# Microcontroller.net
KiCad netlist of a schematic drawn in Altium Designer
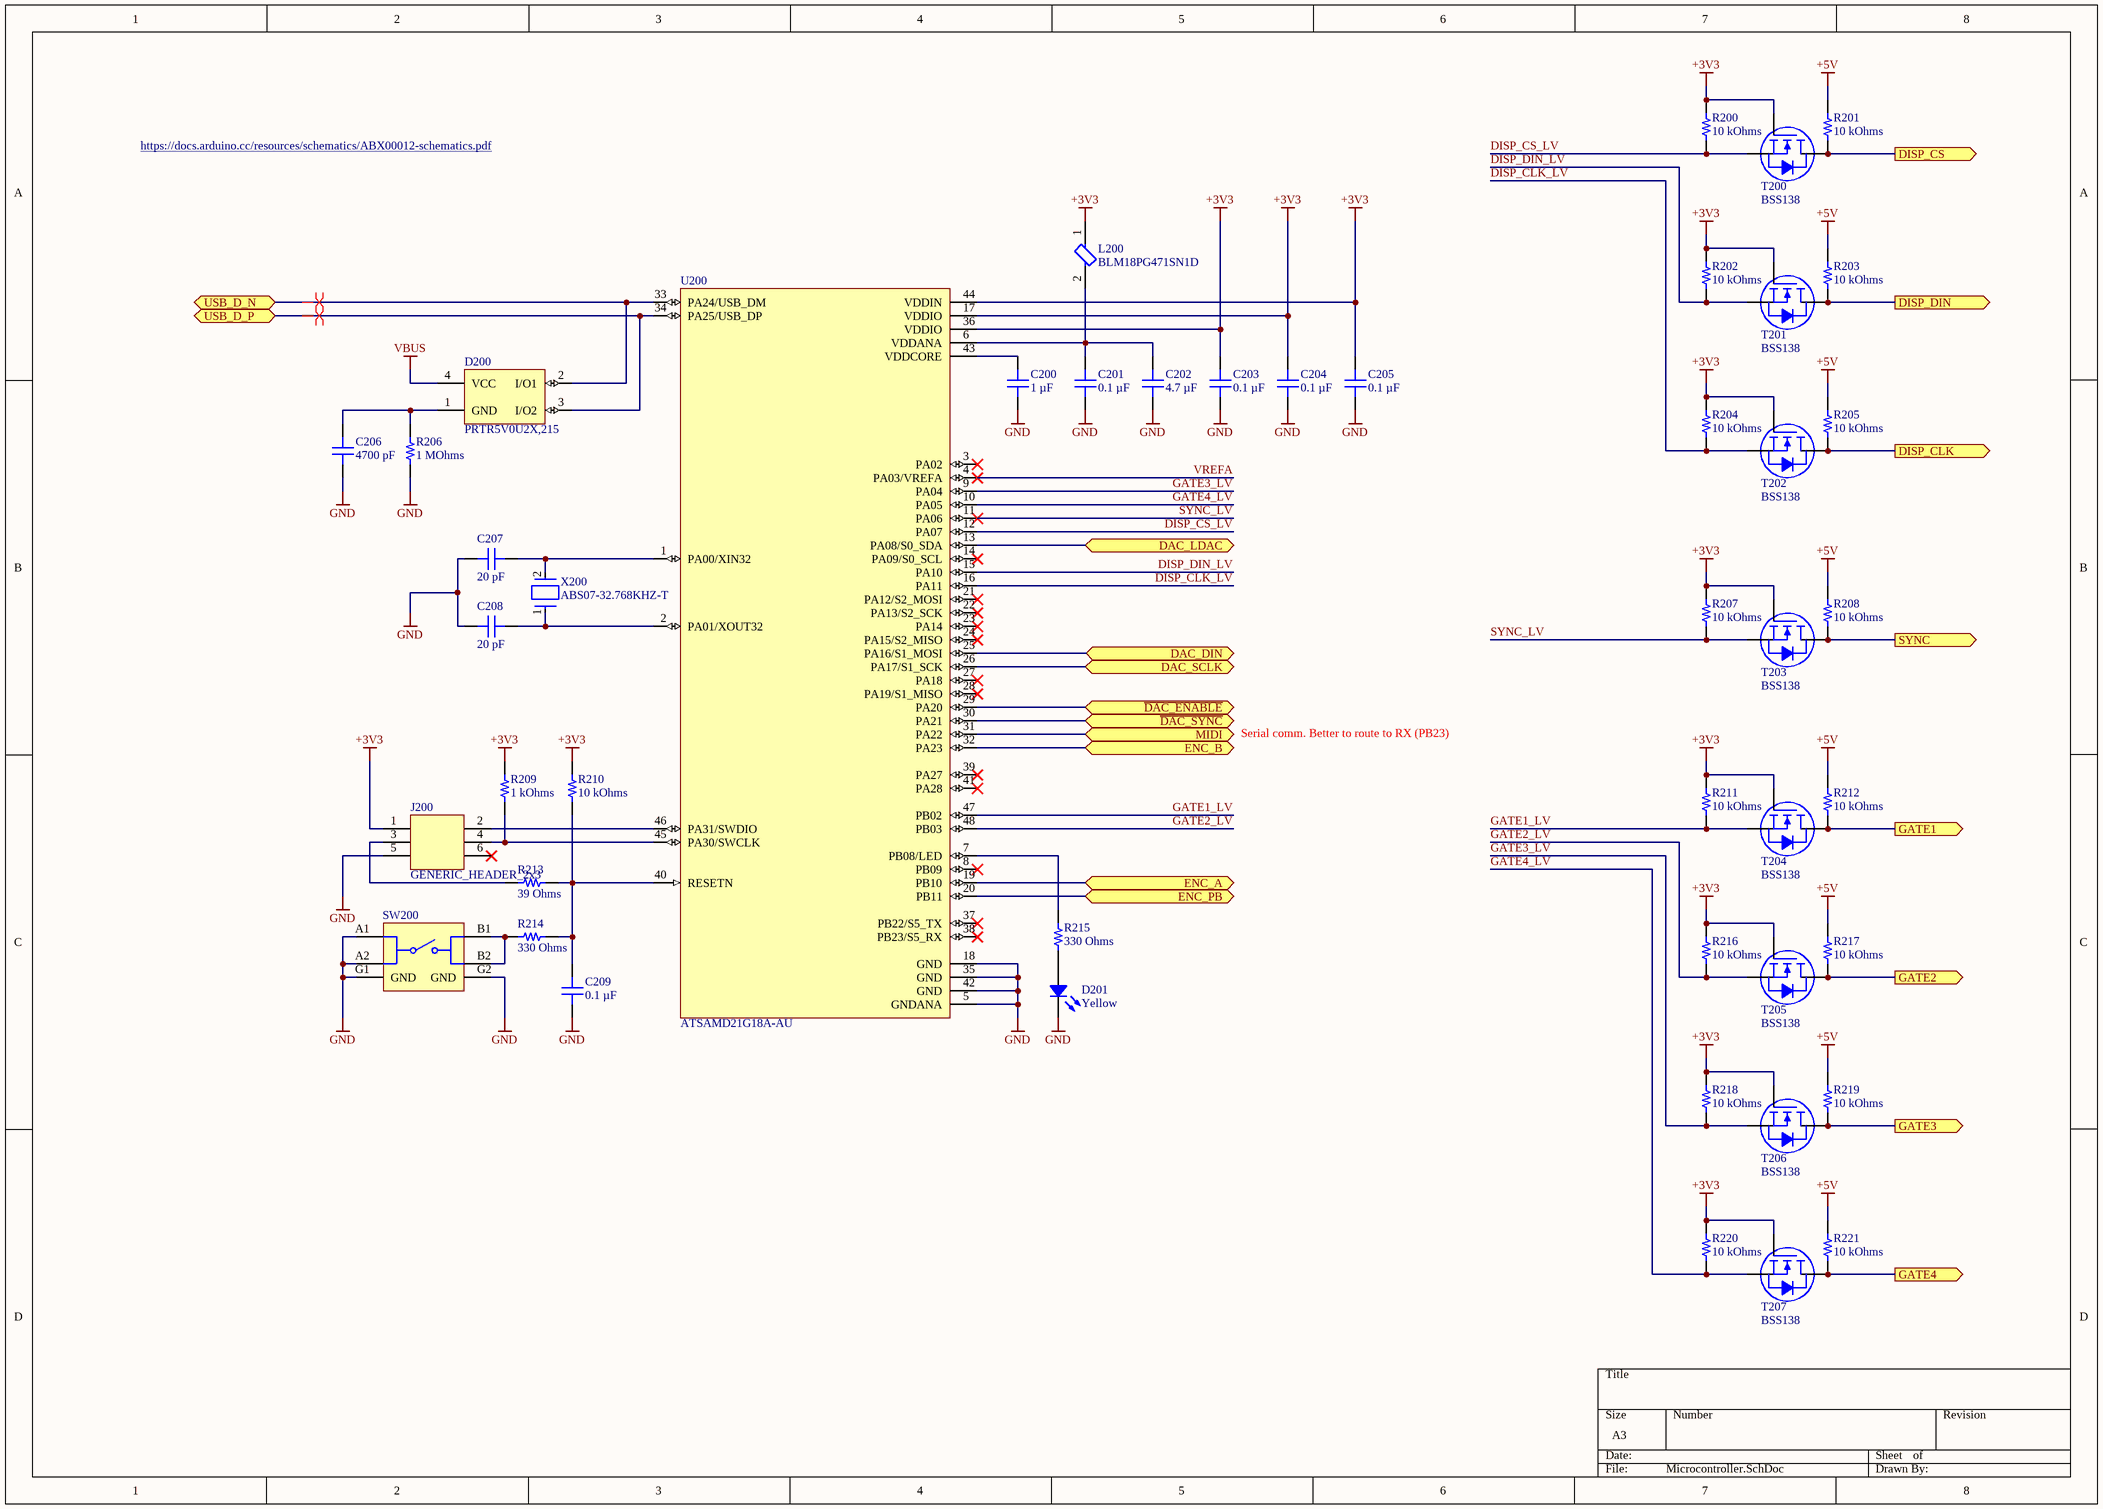
[diagram p0: Microcontroller.SchDoc]

(export (version "E")
  (design (tool "Eeschema 10.0.6"))
  (components
    (comp (ref "C200")
      (value "1 µF")
      (footprint "CAP 0603_1608")
      (description "CAP CER 1UF 10V X7R 0603")
      (fields (field (name "PART NUMBER") "CC0603KRX7R6BB105") (field (name "MANUFACTURER") "Yageo"))
      (libsource (lib "Celestial Altium Library") (part "Capacitor"))
    )
    (comp (ref "C201")
      (value "0.1 µF")
      (footprint "CAP 0603_1608")
      (description "CAP CER 0.1UF 16V X7R 0603")
      (fields (field (name "PART NUMBER") "CS0603KRX7R7BB104") (field (name "MANUFACTURER") "Yageo"))
      (libsource (lib "Celestial Altium Library") (part "Capacitor"))
    )
    (comp (ref "C202")
      (value "4.7 µF")
      (footprint "CAP 0603_1608")
      (description "CAP CER 4.7UF 10V X5R 0603")
      (fields (field (name "PART NUMBER") "CC0603MRX5R6BB475") (field (name "MANUFACTURER") "Yageo"))
      (libsource (lib "Celestial Altium Library") (part "Capacitor"))
    )
    (comp (ref "C203")
      (value "0.1 µF")
      (footprint "CAP 0603_1608")
      (description "CAP CER 0.1UF 16V X7R 0603")
      (fields (field (name "PART NUMBER") "CS0603KRX7R7BB104") (field (name "MANUFACTURER") "Yageo"))
      (libsource (lib "Celestial Altium Library") (part "Capacitor"))
    )
    (comp (ref "C204")
      (value "0.1 µF")
      (footprint "CAP 0603_1608")
      (description "CAP CER 0.1UF 16V X7R 0603")
      (fields (field (name "PART NUMBER") "CS0603KRX7R7BB104") (field (name "MANUFACTURER") "Yageo"))
      (libsource (lib "Celestial Altium Library") (part "Capacitor"))
    )
    (comp (ref "C205")
      (value "0.1 µF")
      (footprint "CAP 0603_1608")
      (description "CAP CER 0.1UF 16V X7R 0603")
      (fields (field (name "PART NUMBER") "CS0603KRX7R7BB104") (field (name "MANUFACTURER") "Yageo"))
      (libsource (lib "Celestial Altium Library") (part "Capacitor"))
    )
    (comp (ref "C206")
      (value "4700 pF")
      (footprint "CAP 0603_1608")
      (description "CAP CER 4700PF 50V X7R 0603")
      (fields (field (name "PART NUMBER") "CC0603JRX7R9BB472") (field (name "MANUFACTURER") "Yageo"))
      (libsource (lib "Celestial Altium Library") (part "Capacitor"))
    )
    (comp (ref "C207")
      (value "20 pF")
      (footprint "CAP 0603_1608")
      (description "CAP CER 20PF 50V C0G/NPO 0603")
      (fields (field (name "PART NUMBER") "CC0603JRNPO9BN200") (field (name "MANUFACTURER") "Yageo"))
      (libsource (lib "Celestial Altium Library") (part "Capacitor"))
    )
    (comp (ref "C208")
      (value "20 pF")
      (footprint "CAP 0603_1608")
      (description "CAP CER 20PF 50V C0G/NPO 0603")
      (fields (field (name "PART NUMBER") "CC0603JRNPO9BN200") (field (name "MANUFACTURER") "Yageo"))
      (libsource (lib "Celestial Altium Library") (part "Capacitor"))
    )
    (comp (ref "C209")
      (value "0.1 µF")
      (footprint "CAP 0603_1608")
      (description "CAP CER 0.1UF 16V X7R 0603")
      (fields (field (name "PART NUMBER") "CS0603KRX7R7BB104") (field (name "MANUFACTURER") "Yageo"))
      (libsource (lib "Celestial Altium Library") (part "Capacitor"))
    )
    (comp (ref "D200")
      (value "PRTR5V0U2X,215")
      (footprint "NXP-SOT143B-4_V")
      (fields (field (name "MANUFACTURER") "NXP Semiconductors"))
      (libsource (lib "LabratsSynthLib") (part "PRTR5V0U2X,215"))
    )
    (comp (ref "D201")
      (value "Yellow")
      (footprint "LED 0603_1608 YELLOW")
      (description "LED YELLOW 0603 SMD")
      (fields (field (name "PART NUMBER") "5990040007F") (field (name "MANUFACTURER") "Dialight"))
      (libsource (lib "Celestial Altium Library") (part "LED"))
    )
    (comp (ref "J200")
      (value "GENERIC_HEADER_2x3")
      (footprint "HEADER_2x3_TH_MALE")
      (libsource (lib "LabratsSynthLib") (part "GENERIC_HEADER_2x3"))
    )
    (comp (ref "L200")
      (value "BLM18PG471SN1D")
      (footprint "FP-BLM18-0_15-t0_8-MFG")
      (description "Chip Ferrite Bead, 0603, 470Ω @ 100MHz, 0.2Ω, 25%, 1A")
      (fields (field (name "TOLERANCE") "25%"))
      (libsource (lib "Altium Content Vault") (part "5f30dd21d616792df468990f7003faa"))
    )
    (comp (ref "R200")
      (value "10 kOhms")
      (footprint "RES 0603_1608")
      (description "RES SMD 10K OHM 1% 1/10W 0603")
      (fields (field (name "PART NUMBER") "CRCW060310K0FKTA") (field (name "MANUFACTURER") "Vishay Dale"))
      (libsource (lib "Celestial Altium Library") (part "Resistor"))
    )
    (comp (ref "R201")
      (value "10 kOhms")
      (footprint "RES 0603_1608")
      (description "RES SMD 10K OHM 1% 1/10W 0603")
      (fields (field (name "PART NUMBER") "CRCW060310K0FKTA") (field (name "MANUFACTURER") "Vishay Dale"))
      (libsource (lib "Celestial Altium Library") (part "Resistor"))
    )
    (comp (ref "R202")
      (value "10 kOhms")
      (footprint "RES 0603_1608")
      (description "RES SMD 10K OHM 1% 1/10W 0603")
      (fields (field (name "PART NUMBER") "CRCW060310K0FKTA") (field (name "MANUFACTURER") "Vishay Dale"))
      (libsource (lib "Celestial Altium Library") (part "Resistor"))
    )
    (comp (ref "R203")
      (value "10 kOhms")
      (footprint "RES 0603_1608")
      (description "RES SMD 10K OHM 1% 1/10W 0603")
      (fields (field (name "PART NUMBER") "CRCW060310K0FKTA") (field (name "MANUFACTURER") "Vishay Dale"))
      (libsource (lib "Celestial Altium Library") (part "Resistor"))
    )
    (comp (ref "R204")
      (value "10 kOhms")
      (footprint "RES 0603_1608")
      (description "RES SMD 10K OHM 1% 1/10W 0603")
      (fields (field (name "PART NUMBER") "CRCW060310K0FKTA") (field (name "MANUFACTURER") "Vishay Dale"))
      (libsource (lib "Celestial Altium Library") (part "Resistor"))
    )
    (comp (ref "R205")
      (value "10 kOhms")
      (footprint "RES 0603_1608")
      (description "RES SMD 10K OHM 1% 1/10W 0603")
      (fields (field (name "PART NUMBER") "CRCW060310K0FKTA") (field (name "MANUFACTURER") "Vishay Dale"))
      (libsource (lib "Celestial Altium Library") (part "Resistor"))
    )
    (comp (ref "R206")
      (value "1 MOhms")
      (footprint "RES 0603_1608")
      (description "RES SMD 1M OHM 1% 1/10W 0603")
      (fields (field (name "PART NUMBER") "CRCW06031M00FKEA") (field (name "MANUFACTURER") "Vishay Dale"))
      (libsource (lib "Celestial Altium Library") (part "Resistor"))
    )
    (comp (ref "R207")
      (value "10 kOhms")
      (footprint "RES 0603_1608")
      (description "RES SMD 10K OHM 1% 1/10W 0603")
      (fields (field (name "PART NUMBER") "CRCW060310K0FKTA") (field (name "MANUFACTURER") "Vishay Dale"))
      (libsource (lib "Celestial Altium Library") (part "Resistor"))
    )
    (comp (ref "R208")
      (value "10 kOhms")
      (footprint "RES 0603_1608")
      (description "RES SMD 10K OHM 1% 1/10W 0603")
      (fields (field (name "PART NUMBER") "CRCW060310K0FKTA") (field (name "MANUFACTURER") "Vishay Dale"))
      (libsource (lib "Celestial Altium Library") (part "Resistor"))
    )
    (comp (ref "R209")
      (value "1 kOhms")
      (footprint "RES 0603_1608")
      (description "RES SMD 1K OHM 1% 1/10W 0603")
      (fields (field (name "PART NUMBER") "CRCW06031K00FKEB") (field (name "MANUFACTURER") "Vishay Dale"))
      (libsource (lib "Celestial Altium Library") (part "Resistor"))
    )
    (comp (ref "R210")
      (value "10 kOhms")
      (footprint "RES 0603_1608")
      (description "RES SMD 10K OHM 1% 1/10W 0603")
      (fields (field (name "PART NUMBER") "CRCW060310K0FKTA") (field (name "MANUFACTURER") "Vishay Dale"))
      (libsource (lib "Celestial Altium Library") (part "Resistor"))
    )
    (comp (ref "R211")
      (value "10 kOhms")
      (footprint "RES 0603_1608")
      (description "RES SMD 10K OHM 1% 1/10W 0603")
      (fields (field (name "PART NUMBER") "CRCW060310K0FKTA") (field (name "MANUFACTURER") "Vishay Dale"))
      (libsource (lib "Celestial Altium Library") (part "Resistor"))
    )
    (comp (ref "R212")
      (value "10 kOhms")
      (footprint "RES 0603_1608")
      (description "RES SMD 10K OHM 1% 1/10W 0603")
      (fields (field (name "PART NUMBER") "CRCW060310K0FKTA") (field (name "MANUFACTURER") "Vishay Dale"))
      (libsource (lib "Celestial Altium Library") (part "Resistor"))
    )
    (comp (ref "R213")
      (value "39 Ohms")
      (footprint "RES 0603_1608")
      (description "RES SMD 39 OHM 1% 1/10W 0603")
      (fields (field (name "PART NUMBER") "CRCW060339R0FKEA") (field (name "MANUFACTURER") "Vishay Dale"))
      (libsource (lib "Celestial Altium Library") (part "Resistor"))
    )
    (comp (ref "R214")
      (value "330 Ohms")
      (footprint "RES 0603_1608")
      (description "RES 330 OHM 1% 1/10W 0603")
      (fields (field (name "PART NUMBER") "CRCW0603330RFKEAC") (field (name "MANUFACTURER") "Vishay Dale"))
      (libsource (lib "Celestial Altium Library") (part "Resistor"))
    )
    (comp (ref "R215")
      (value "330 Ohms")
      (footprint "RES 0603_1608")
      (description "RES 330 OHM 1% 1/10W 0603")
      (fields (field (name "PART NUMBER") "CRCW0603330RFKEAC") (field (name "MANUFACTURER") "Vishay Dale"))
      (libsource (lib "Celestial Altium Library") (part "Resistor"))
    )
    (comp (ref "R216")
      (value "10 kOhms")
      (footprint "RES 0603_1608")
      (description "RES SMD 10K OHM 1% 1/10W 0603")
      (fields (field (name "PART NUMBER") "CRCW060310K0FKTA") (field (name "MANUFACTURER") "Vishay Dale"))
      (libsource (lib "Celestial Altium Library") (part "Resistor"))
    )
    (comp (ref "R217")
      (value "10 kOhms")
      (footprint "RES 0603_1608")
      (description "RES SMD 10K OHM 1% 1/10W 0603")
      (fields (field (name "PART NUMBER") "CRCW060310K0FKTA") (field (name "MANUFACTURER") "Vishay Dale"))
      (libsource (lib "Celestial Altium Library") (part "Resistor"))
    )
    (comp (ref "R218")
      (value "10 kOhms")
      (footprint "RES 0603_1608")
      (description "RES SMD 10K OHM 1% 1/10W 0603")
      (fields (field (name "PART NUMBER") "CRCW060310K0FKTA") (field (name "MANUFACTURER") "Vishay Dale"))
      (libsource (lib "Celestial Altium Library") (part "Resistor"))
    )
    (comp (ref "R219")
      (value "10 kOhms")
      (footprint "RES 0603_1608")
      (description "RES SMD 10K OHM 1% 1/10W 0603")
      (fields (field (name "PART NUMBER") "CRCW060310K0FKTA") (field (name "MANUFACTURER") "Vishay Dale"))
      (libsource (lib "Celestial Altium Library") (part "Resistor"))
    )
    (comp (ref "R220")
      (value "10 kOhms")
      (footprint "RES 0603_1608")
      (description "RES SMD 10K OHM 1% 1/10W 0603")
      (fields (field (name "PART NUMBER") "CRCW060310K0FKTA") (field (name "MANUFACTURER") "Vishay Dale"))
      (libsource (lib "Celestial Altium Library") (part "Resistor"))
    )
    (comp (ref "R221")
      (value "10 kOhms")
      (footprint "RES 0603_1608")
      (description "RES SMD 10K OHM 1% 1/10W 0603")
      (fields (field (name "PART NUMBER") "CRCW060310K0FKTA") (field (name "MANUFACTURER") "Vishay Dale"))
      (libsource (lib "Celestial Altium Library") (part "Resistor"))
    )
    (comp (ref "SW200")
      (value "435171014816")
      (footprint "435171014816")
      (description "Tactile Switch, Spst-no, 0.05A, 12V, SMD;")
      (libsource (lib "Altium Content Vault") (part "SPST-NO_4P_2GND"))
    )
    (comp (ref "T200")
      (value "BSS138")
      (footprint "ON SEMI SOT-23-3")
      (description "MOSFET N-CH 50V 220MA SOT-23")
      (fields (field (name "MANUFACTURER") "ON Semiconductor"))
      (libsource (lib "Celestial Altium Library") (part "ON SEMI MOSFET N-CH SOT-23-3"))
    )
    (comp (ref "T201")
      (value "BSS138")
      (footprint "ON SEMI SOT-23-3")
      (description "MOSFET N-CH 50V 220MA SOT-23")
      (fields (field (name "MANUFACTURER") "ON Semiconductor"))
      (libsource (lib "Celestial Altium Library") (part "ON SEMI MOSFET N-CH SOT-23-3"))
    )
    (comp (ref "T202")
      (value "BSS138")
      (footprint "ON SEMI SOT-23-3")
      (description "MOSFET N-CH 50V 220MA SOT-23")
      (fields (field (name "MANUFACTURER") "ON Semiconductor"))
      (libsource (lib "Celestial Altium Library") (part "ON SEMI MOSFET N-CH SOT-23-3"))
    )
    (comp (ref "T203")
      (value "BSS138")
      (footprint "ON SEMI SOT-23-3")
      (description "MOSFET N-CH 50V 220MA SOT-23")
      (fields (field (name "MANUFACTURER") "ON Semiconductor"))
      (libsource (lib "Celestial Altium Library") (part "ON SEMI MOSFET N-CH SOT-23-3"))
    )
    (comp (ref "T204")
      (value "BSS138")
      (footprint "ON SEMI SOT-23-3")
      (description "MOSFET N-CH 50V 220MA SOT-23")
      (fields (field (name "MANUFACTURER") "ON Semiconductor"))
      (libsource (lib "Celestial Altium Library") (part "ON SEMI MOSFET N-CH SOT-23-3"))
    )
    (comp (ref "T205")
      (value "BSS138")
      (footprint "ON SEMI SOT-23-3")
      (description "MOSFET N-CH 50V 220MA SOT-23")
      (fields (field (name "MANUFACTURER") "ON Semiconductor"))
      (libsource (lib "Celestial Altium Library") (part "ON SEMI MOSFET N-CH SOT-23-3"))
    )
    (comp (ref "T206")
      (value "BSS138")
      (footprint "ON SEMI SOT-23-3")
      (description "MOSFET N-CH 50V 220MA SOT-23")
      (fields (field (name "MANUFACTURER") "ON Semiconductor"))
      (libsource (lib "Celestial Altium Library") (part "ON SEMI MOSFET N-CH SOT-23-3"))
    )
    (comp (ref "T207")
      (value "BSS138")
      (footprint "ON SEMI SOT-23-3")
      (description "MOSFET N-CH 50V 220MA SOT-23")
      (fields (field (name "MANUFACTURER") "ON Semiconductor"))
      (libsource (lib "Celestial Altium Library") (part "ON SEMI MOSFET N-CH SOT-23-3"))
    )
    (comp (ref "U200")
      (value "ATSAMD21G18A-AU")
      (footprint "ATML-TQFP48")
      (fields (field (name "MANUFACTURER") "Atmel"))
      (libsource (lib "LabratsSynthLib") (part "ATSAMD21G18A-AU"))
    )
    (comp (ref "X200")
      (value "ABS07-32.768KHZ-T")
      (footprint "FP-ABS07-MFG")
      (description "Crystal 32.768kHz ±20ppm (Tol) 12.5pF FUND 70kΩ 2-Pin CSMD T/R")
      (fields (field (name "TOLERANCE") "20ppm"))
      (libsource (lib "Altium Content Vault") (part "c23a69dc6c9e2f18f2079038eb95dd1"))
    )
  )
  (nets
    (net (code "1") (name "+3V3") (class "Default")
      (node (ref "C203") (pin "2") (pinfunction "2_2") (pintype "passive"))
      (node (ref "C204") (pin "2") (pinfunction "2_2") (pintype "passive"))
      (node (ref "C205") (pin "2") (pinfunction "2_2") (pintype "passive"))
      (node (ref "J200") (pin "1") (pinfunction "1_1") (pintype "passive"))
      (node (ref "L200") (pin "1") (pinfunction "1_1") (pintype "passive"))
      (node (ref "R200") (pin "2") (pinfunction "2_2") (pintype "passive"))
      (node (ref "R202") (pin "2") (pinfunction "2_2") (pintype "passive"))
      (node (ref "R204") (pin "2") (pinfunction "2_2") (pintype "passive"))
      (node (ref "R207") (pin "2") (pinfunction "2_2") (pintype "passive"))
      (node (ref "R209") (pin "2") (pinfunction "2_2") (pintype "passive"))
      (node (ref "R210") (pin "2") (pinfunction "2_2") (pintype "passive"))
      (node (ref "R211") (pin "2") (pinfunction "2_2") (pintype "passive"))
      (node (ref "R216") (pin "2") (pinfunction "2_2") (pintype "passive"))
      (node (ref "R218") (pin "2") (pinfunction "2_2") (pintype "passive"))
      (node (ref "R220") (pin "2") (pinfunction "2_2") (pintype "passive"))
      (node (ref "T200") (pin "1") (pinfunction "G_1") (pintype "passive"))
      (node (ref "T201") (pin "1") (pinfunction "G_1") (pintype "passive"))
      (node (ref "T202") (pin "1") (pinfunction "G_1") (pintype "passive"))
      (node (ref "T203") (pin "1") (pinfunction "G_1") (pintype "passive"))
      (node (ref "T204") (pin "1") (pinfunction "G_1") (pintype "passive"))
      (node (ref "T205") (pin "1") (pinfunction "G_1") (pintype "passive"))
      (node (ref "T206") (pin "1") (pinfunction "G_1") (pintype "passive"))
      (node (ref "T207") (pin "1") (pinfunction "G_1") (pintype "passive"))
      (node (ref "U200") (pin "17") (pinfunction "VDDIO_17") (pintype "power_in"))
      (node (ref "U200") (pin "36") (pinfunction "VDDIO_36") (pintype "power_in"))
      (node (ref "U200") (pin "44") (pinfunction "VDDIN_44") (pintype "power_in"))
    )
    (net (code "2") (name "+5V") (class "Default")
      (node (ref "R201") (pin "2") (pinfunction "2_2") (pintype "passive"))
      (node (ref "R203") (pin "2") (pinfunction "2_2") (pintype "passive"))
      (node (ref "R205") (pin "2") (pinfunction "2_2") (pintype "passive"))
      (node (ref "R208") (pin "2") (pinfunction "2_2") (pintype "passive"))
      (node (ref "R212") (pin "2") (pinfunction "2_2") (pintype "passive"))
      (node (ref "R217") (pin "2") (pinfunction "2_2") (pintype "passive"))
      (node (ref "R219") (pin "2") (pinfunction "2_2") (pintype "passive"))
      (node (ref "R221") (pin "2") (pinfunction "2_2") (pintype "passive"))
    )
    (net (code "3") (name "/DAC_DIN") (class "Default")
      (node (ref "U200") (pin "25") (pinfunction "PA16/S1_MOSI_25") (pintype "bidirectional"))
    )
    (net (code "4") (name "/DAC_LDAC") (class "Default")
      (node (ref "U200") (pin "13") (pinfunction "PA08/S0_SDA_13") (pintype "bidirectional"))
    )
    (net (code "5") (name "/DAC_SCLK") (class "Default")
      (node (ref "U200") (pin "26") (pinfunction "PA17/S1_SCK_26") (pintype "bidirectional"))
    )
    (net (code "6") (name "/DISP_CLK") (class "Default")
      (node (ref "R205") (pin "1") (pinfunction "1_1") (pintype "passive"))
      (node (ref "T202") (pin "3") (pinfunction "D_3") (pintype "passive"))
    )
    (net (code "7") (name "/DISP_CLK_LV") (class "Default")
      (node (ref "R204") (pin "1") (pinfunction "1_1") (pintype "passive"))
      (node (ref "T202") (pin "2") (pinfunction "S_2") (pintype "passive"))
      (node (ref "U200") (pin "16") (pinfunction "PA11_16") (pintype "bidirectional"))
    )
    (net (code "8") (name "/DISP_CS") (class "Default")
      (node (ref "R201") (pin "1") (pinfunction "1_1") (pintype "passive"))
      (node (ref "T200") (pin "3") (pinfunction "D_3") (pintype "passive"))
    )
    (net (code "9") (name "/DISP_CS_LV") (class "Default")
      (node (ref "R200") (pin "1") (pinfunction "1_1") (pintype "passive"))
      (node (ref "T200") (pin "2") (pinfunction "S_2") (pintype "passive"))
      (node (ref "U200") (pin "12") (pinfunction "PA07_12") (pintype "bidirectional"))
    )
    (net (code "10") (name "/DISP_DIN") (class "Default")
      (node (ref "R203") (pin "1") (pinfunction "1_1") (pintype "passive"))
      (node (ref "T201") (pin "3") (pinfunction "D_3") (pintype "passive"))
    )
    (net (code "11") (name "/DISP_DIN_LV") (class "Default")
      (node (ref "R202") (pin "1") (pinfunction "1_1") (pintype "passive"))
      (node (ref "T201") (pin "2") (pinfunction "S_2") (pintype "passive"))
      (node (ref "U200") (pin "15") (pinfunction "PA10_15") (pintype "bidirectional"))
    )
    (net (code "12") (name "/ENC_A") (class "Default")
      (node (ref "U200") (pin "19") (pinfunction "PB10_19") (pintype "bidirectional"))
    )
    (net (code "13") (name "/ENC_B") (class "Default")
      (node (ref "U200") (pin "32") (pinfunction "PA23_32") (pintype "bidirectional"))
    )
    (net (code "14") (name "/ENC_PB") (class "Default")
      (node (ref "U200") (pin "20") (pinfunction "PB11_20") (pintype "bidirectional"))
    )
    (net (code "15") (name "/GATE1") (class "Default")
      (node (ref "R212") (pin "1") (pinfunction "1_1") (pintype "passive"))
      (node (ref "T204") (pin "3") (pinfunction "D_3") (pintype "passive"))
    )
    (net (code "16") (name "/GATE1_LV") (class "Default")
      (node (ref "R211") (pin "1") (pinfunction "1_1") (pintype "passive"))
      (node (ref "T204") (pin "2") (pinfunction "S_2") (pintype "passive"))
      (node (ref "U200") (pin "47") (pinfunction "PB02_47") (pintype "bidirectional"))
    )
    (net (code "17") (name "/GATE2") (class "Default")
      (node (ref "R217") (pin "1") (pinfunction "1_1") (pintype "passive"))
      (node (ref "T205") (pin "3") (pinfunction "D_3") (pintype "passive"))
    )
    (net (code "18") (name "/GATE2_LV") (class "Default")
      (node (ref "R216") (pin "1") (pinfunction "1_1") (pintype "passive"))
      (node (ref "T205") (pin "2") (pinfunction "S_2") (pintype "passive"))
      (node (ref "U200") (pin "48") (pinfunction "PB03_48") (pintype "bidirectional"))
    )
    (net (code "19") (name "/GATE3") (class "Default")
      (node (ref "R219") (pin "1") (pinfunction "1_1") (pintype "passive"))
      (node (ref "T206") (pin "3") (pinfunction "D_3") (pintype "passive"))
    )
    (net (code "20") (name "/GATE3_LV") (class "Default")
      (node (ref "R218") (pin "1") (pinfunction "1_1") (pintype "passive"))
      (node (ref "T206") (pin "2") (pinfunction "S_2") (pintype "passive"))
      (node (ref "U200") (pin "9") (pinfunction "PA04_9") (pintype "bidirectional"))
    )
    (net (code "21") (name "/GATE4") (class "Default")
      (node (ref "R221") (pin "1") (pinfunction "1_1") (pintype "passive"))
      (node (ref "T207") (pin "3") (pinfunction "D_3") (pintype "passive"))
    )
    (net (code "22") (name "/GATE4_LV") (class "Default")
      (node (ref "R220") (pin "1") (pinfunction "1_1") (pintype "passive"))
      (node (ref "T207") (pin "2") (pinfunction "S_2") (pintype "passive"))
      (node (ref "U200") (pin "10") (pinfunction "PA05_10") (pintype "bidirectional"))
    )
    (net (code "23") (name "/MIDI") (class "Default")
      (node (ref "U200") (pin "31") (pinfunction "PA22_31") (pintype "bidirectional"))
    )
    (net (code "24") (name "/SYNC") (class "Default")
      (node (ref "R208") (pin "1") (pinfunction "1_1") (pintype "passive"))
      (node (ref "T203") (pin "3") (pinfunction "D_3") (pintype "passive"))
    )
    (net (code "25") (name "/SYNC_LV") (class "Default")
      (node (ref "R207") (pin "1") (pinfunction "1_1") (pintype "passive"))
      (node (ref "T203") (pin "2") (pinfunction "S_2") (pintype "passive"))
      (node (ref "U200") (pin "11") (pinfunction "PA06_11") (pintype "bidirectional"))
    )
    (net (code "26") (name "/USB_D_N") (class "Default")
      (node (ref "D200") (pin "2") (pinfunction "I/O1_2") (pintype "bidirectional"))
      (node (ref "U200") (pin "33") (pinfunction "PA24/USB_DM_33") (pintype "bidirectional"))
    )
    (net (code "27") (name "/USB_D_P") (class "Default")
      (node (ref "D200") (pin "3") (pinfunction "I/O2_3") (pintype "bidirectional"))
      (node (ref "U200") (pin "34") (pinfunction "PA25/USB_DP_34") (pintype "bidirectional"))
    )
    (net (code "28") (name "/VREFA") (class "Default")
      (node (ref "U200") (pin "4") (pinfunction "PA03/VREFA_4") (pintype "bidirectional+no_connect"))
    )
    (net (code "29") (name "/~{DAC_ENABLE}") (class "Default")
      (node (ref "U200") (pin "29") (pinfunction "PA20_29") (pintype "bidirectional"))
    )
    (net (code "30") (name "/~{DAC_SYNC}") (class "Default")
      (node (ref "U200") (pin "30") (pinfunction "PA21_30") (pintype "bidirectional"))
    )
    (net (code "31") (name "GND") (class "Default")
      (node (ref "C200") (pin "1") (pinfunction "1_1") (pintype "passive"))
      (node (ref "C201") (pin "1") (pinfunction "1_1") (pintype "passive"))
      (node (ref "C202") (pin "1") (pinfunction "1_1") (pintype "passive"))
      (node (ref "C203") (pin "1") (pinfunction "1_1") (pintype "passive"))
      (node (ref "C204") (pin "1") (pinfunction "1_1") (pintype "passive"))
      (node (ref "C205") (pin "1") (pinfunction "1_1") (pintype "passive"))
      (node (ref "C206") (pin "1") (pinfunction "1_1") (pintype "passive"))
      (node (ref "C207") (pin "1") (pinfunction "1_1") (pintype "passive"))
      (node (ref "C208") (pin "1") (pinfunction "1_1") (pintype "passive"))
      (node (ref "C209") (pin "1") (pinfunction "1_1") (pintype "passive"))
      (node (ref "D201") (pin "2") (pinfunction "2_2") (pintype "passive"))
      (node (ref "J200") (pin "5") (pinfunction "5_5") (pintype "passive"))
      (node (ref "R206") (pin "1") (pinfunction "1_1") (pintype "passive"))
      (node (ref "SW200") (pin "A1") (pinfunction "A1_A1") (pintype "passive"))
      (node (ref "SW200") (pin "A2") (pinfunction "A2_A2") (pintype "passive"))
      (node (ref "SW200") (pin "G1") (pinfunction "GND_G1") (pintype "passive"))
      (node (ref "SW200") (pin "G2") (pinfunction "GND_G2") (pintype "passive"))
      (node (ref "U200") (pin "18") (pinfunction "GND_18") (pintype "power_in"))
      (node (ref "U200") (pin "35") (pinfunction "GND_35") (pintype "power_in"))
      (node (ref "U200") (pin "42") (pinfunction "GND_42") (pintype "power_in"))
      (node (ref "U200") (pin "5") (pinfunction "GNDANA_5") (pintype "power_in"))
    )
    (net (code "32") (name "Net-(D200-GND)") (class "Default")
      (node (ref "C206") (pin "2") (pinfunction "2_2") (pintype "passive"))
      (node (ref "D200") (pin "1") (pinfunction "GND_1") (pintype "power_in"))
      (node (ref "R206") (pin "2") (pinfunction "2_2") (pintype "passive"))
    )
    (net (code "33") (name "Net-(D201-Pad1)") (class "Default")
      (node (ref "D201") (pin "1") (pinfunction "1_1") (pintype "passive"))
      (node (ref "R215") (pin "2") (pinfunction "2_2") (pintype "passive"))
    )
    (net (code "34") (name "Net-(J200-Pad3)") (class "Default")
      (node (ref "J200") (pin "3") (pinfunction "3_3") (pintype "passive"))
      (node (ref "R213") (pin "1") (pinfunction "1_1") (pintype "passive"))
    )
    (net (code "35") (name "Net-(R214-Pad1)") (class "Default")
      (node (ref "R214") (pin "1") (pinfunction "1_1") (pintype "passive"))
      (node (ref "SW200") (pin "B1") (pinfunction "B1_B1") (pintype "passive"))
      (node (ref "SW200") (pin "B2") (pinfunction "B2_B2") (pintype "passive"))
    )
    (net (code "36") (name "Net-(U200-PA00{slash}XIN32)") (class "Default")
      (node (ref "C207") (pin "2") (pinfunction "2_2") (pintype "passive"))
      (node (ref "U200") (pin "1") (pinfunction "PA00/XIN32_1") (pintype "bidirectional"))
      (node (ref "X200") (pin "2") (pinfunction "2_2") (pintype "passive"))
    )
    (net (code "37") (name "Net-(U200-PA01{slash}XOUT32)") (class "Default")
      (node (ref "C208") (pin "2") (pinfunction "2_2") (pintype "passive"))
      (node (ref "U200") (pin "2") (pinfunction "PA01/XOUT32_2") (pintype "bidirectional"))
      (node (ref "X200") (pin "1") (pinfunction "1_1") (pintype "passive"))
    )
    (net (code "38") (name "Net-(U200-PA30{slash}SWCLK)") (class "Default")
      (node (ref "J200") (pin "4") (pinfunction "4_4") (pintype "passive"))
      (node (ref "R209") (pin "1") (pinfunction "1_1") (pintype "passive"))
      (node (ref "U200") (pin "45") (pinfunction "PA30/SWCLK_45") (pintype "bidirectional"))
    )
    (net (code "39") (name "Net-(U200-PA31{slash}SWDIO)") (class "Default")
      (node (ref "J200") (pin "2") (pinfunction "2_2") (pintype "passive"))
      (node (ref "U200") (pin "46") (pinfunction "PA31/SWDIO_46") (pintype "bidirectional"))
    )
    (net (code "40") (name "Net-(U200-PB08{slash}LED)") (class "Default")
      (node (ref "R215") (pin "1") (pinfunction "1_1") (pintype "passive"))
      (node (ref "U200") (pin "7") (pinfunction "PB08/LED_7") (pintype "bidirectional"))
    )
    (net (code "41") (name "Net-(U200-RESETN)") (class "Default")
      (node (ref "C209") (pin "2") (pinfunction "2_2") (pintype "passive"))
      (node (ref "R210") (pin "1") (pinfunction "1_1") (pintype "passive"))
      (node (ref "R213") (pin "2") (pinfunction "2_2") (pintype "passive"))
      (node (ref "R214") (pin "2") (pinfunction "2_2") (pintype "passive"))
      (node (ref "U200") (pin "40") (pinfunction "RESETN_40") (pintype "input"))
    )
    (net (code "42") (name "Net-(U200-VDDANA)") (class "Default")
      (node (ref "C201") (pin "2") (pinfunction "2_2") (pintype "passive"))
      (node (ref "C202") (pin "2") (pinfunction "2_2") (pintype "passive"))
      (node (ref "L200") (pin "2") (pinfunction "2_2") (pintype "passive"))
      (node (ref "U200") (pin "6") (pinfunction "VDDANA_6") (pintype "power_in"))
    )
    (net (code "43") (name "Net-(U200-VDDCORE)") (class "Default")
      (node (ref "C200") (pin "2") (pinfunction "2_2") (pintype "passive"))
      (node (ref "U200") (pin "43") (pinfunction "VDDCORE_43") (pintype "power_in"))
    )
    (net (code "44") (name "VBUS") (class "Default")
      (node (ref "D200") (pin "4") (pinfunction "VCC_4") (pintype "power_in"))
    )
    (net (code "45") (name "unconnected-(J200-Pad6)") (class "Default")
      (node (ref "J200") (pin "6") (pinfunction "6_6") (pintype "passive+no_connect"))
    )
    (net (code "46") (name "unconnected-(U200-PA02-Pad3)") (class "Default")
      (node (ref "U200") (pin "3") (pinfunction "PA02_3") (pintype "bidirectional+no_connect"))
    )
    (net (code "47") (name "unconnected-(U200-PA09{slash}S0_SCL-Pad14)") (class "Default")
      (node (ref "U200") (pin "14") (pinfunction "PA09/S0_SCL_14") (pintype "bidirectional+no_connect"))
    )
    (net (code "48") (name "unconnected-(U200-PA12{slash}S2_MOSI-Pad21)") (class "Default")
      (node (ref "U200") (pin "21") (pinfunction "PA12/S2_MOSI_21") (pintype "bidirectional+no_connect"))
    )
    (net (code "49") (name "unconnected-(U200-PA13{slash}S2_SCK-Pad22)") (class "Default")
      (node (ref "U200") (pin "22") (pinfunction "PA13/S2_SCK_22") (pintype "bidirectional+no_connect"))
    )
    (net (code "50") (name "unconnected-(U200-PA14-Pad23)") (class "Default")
      (node (ref "U200") (pin "23") (pinfunction "PA14_23") (pintype "bidirectional+no_connect"))
    )
    (net (code "51") (name "unconnected-(U200-PA15{slash}S2_MISO-Pad24)") (class "Default")
      (node (ref "U200") (pin "24") (pinfunction "PA15/S2_MISO_24") (pintype "bidirectional+no_connect"))
    )
    (net (code "52") (name "unconnected-(U200-PA18-Pad27)") (class "Default")
      (node (ref "U200") (pin "27") (pinfunction "PA18_27") (pintype "bidirectional+no_connect"))
    )
    (net (code "53") (name "unconnected-(U200-PA19{slash}S1_MISO-Pad28)") (class "Default")
      (node (ref "U200") (pin "28") (pinfunction "PA19/S1_MISO_28") (pintype "bidirectional+no_connect"))
    )
    (net (code "54") (name "unconnected-(U200-PA27-Pad39)") (class "Default")
      (node (ref "U200") (pin "39") (pinfunction "PA27_39") (pintype "bidirectional+no_connect"))
    )
    (net (code "55") (name "unconnected-(U200-PA28-Pad41)") (class "Default")
      (node (ref "U200") (pin "41") (pinfunction "PA28_41") (pintype "bidirectional+no_connect"))
    )
    (net (code "56") (name "unconnected-(U200-PB09-Pad8)") (class "Default")
      (node (ref "U200") (pin "8") (pinfunction "PB09_8") (pintype "bidirectional+no_connect"))
    )
    (net (code "57") (name "unconnected-(U200-PB22{slash}S5_TX-Pad37)") (class "Default")
      (node (ref "U200") (pin "37") (pinfunction "PB22/S5_TX_37") (pintype "bidirectional+no_connect"))
    )
    (net (code "58") (name "unconnected-(U200-PB23{slash}S5_RX-Pad38)") (class "Default")
      (node (ref "U200") (pin "38") (pinfunction "PB23/S5_RX_38") (pintype "bidirectional+no_connect"))
    )
  )
)
